# teensyLC-midi-IO_01.net
KiCad netlist of a schematic drawn in EAGLE
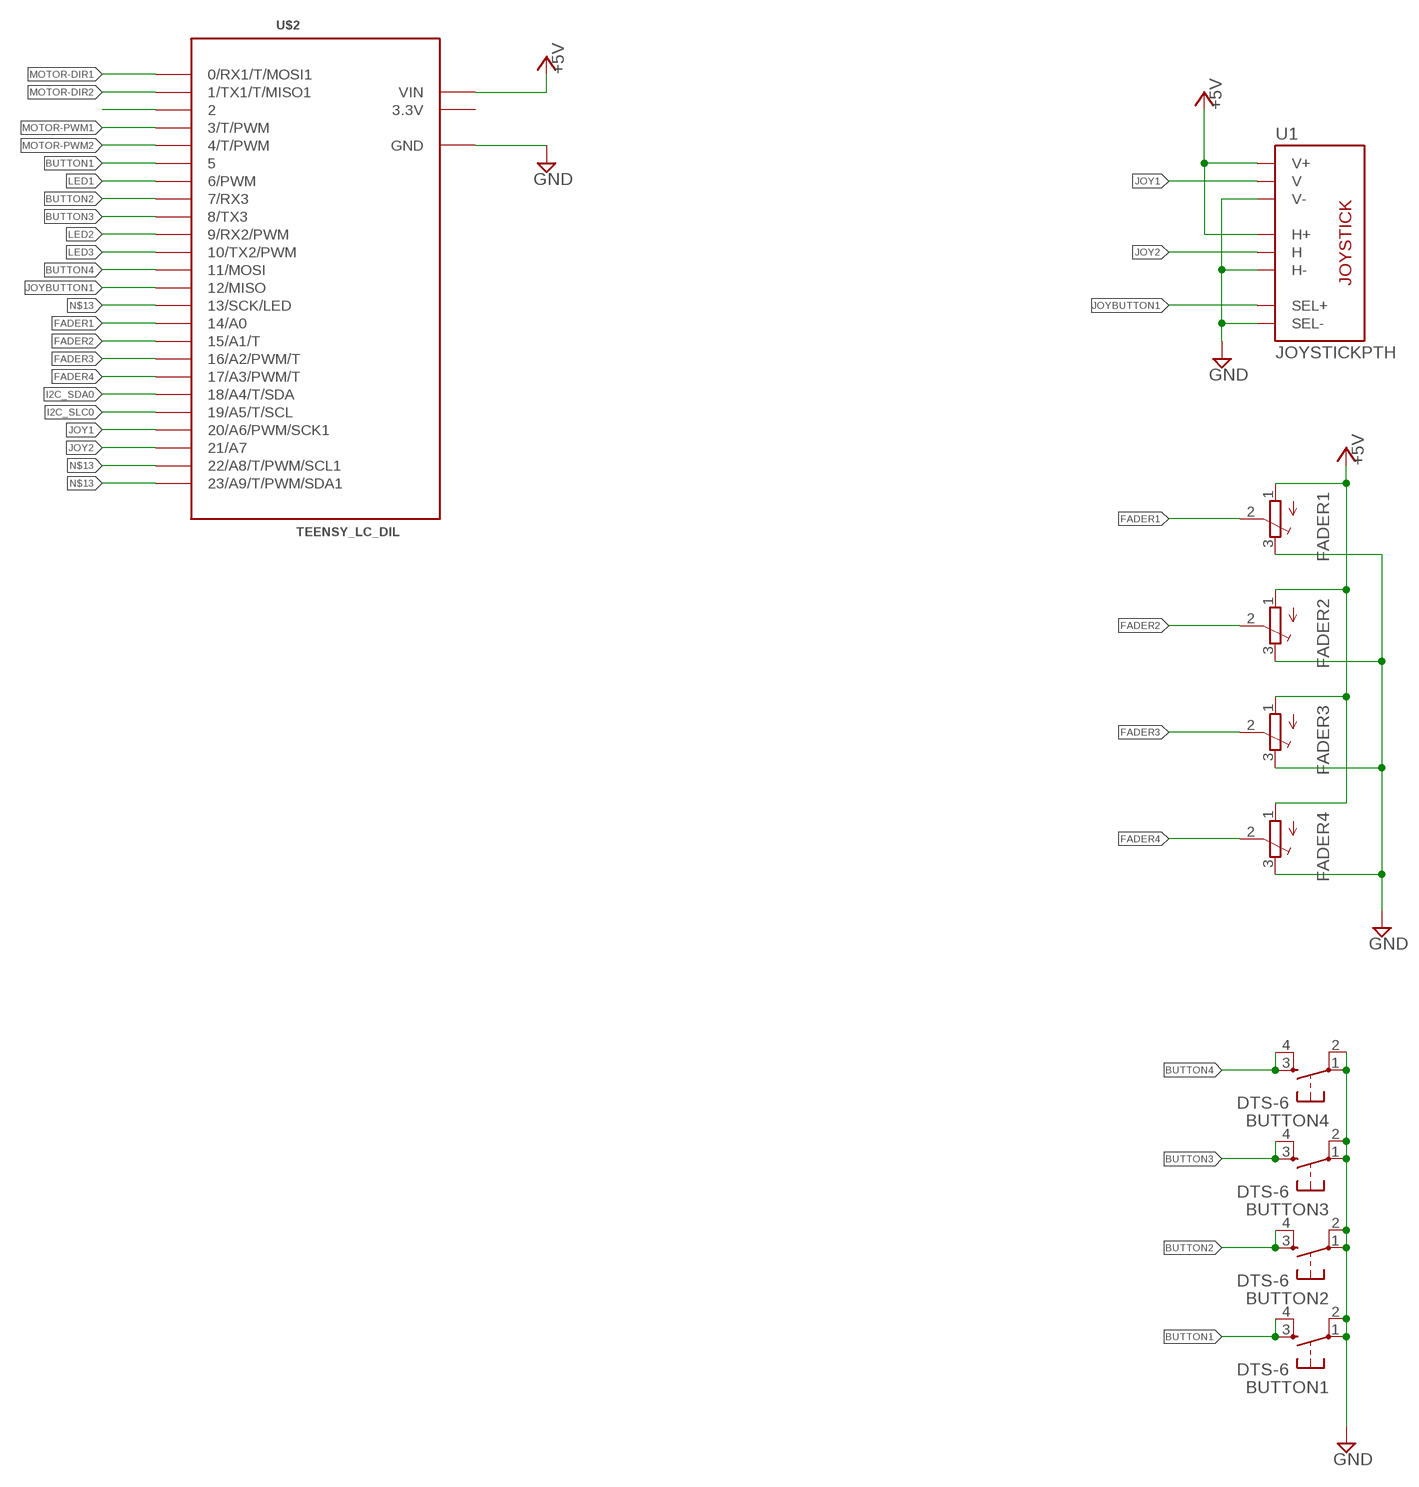
[diagram p0: schematic, sheet 1]

(export (version "E")
  (design (tool "Eeschema 10.0.6"))
  (components
    (comp (ref "BUTTON1")
      (value "DTS-6")
      (footprint "eagle-import:DTS-6")
      (libsource (lib "eagle-import") (part "DTS-6"))
    )
    (comp (ref "BUTTON2")
      (value "DTS-6")
      (footprint "eagle-import:DTS-6")
      (libsource (lib "eagle-import") (part "DTS-6"))
    )
    (comp (ref "BUTTON3")
      (value "DTS-6")
      (footprint "eagle-import:DTS-6")
      (libsource (lib "eagle-import") (part "DTS-6"))
    )
    (comp (ref "BUTTON4")
      (value "DTS-6")
      (footprint "eagle-import:DTS-6")
      (libsource (lib "eagle-import") (part "DTS-6"))
    )
    (comp (ref "FADER1")
      (value "TRIMPOT3386")
      (footprint "eagle-import:TRIM-3386")
      (libsource (lib "eagle-import") (part "TRIMPOT3386"))
    )
    (comp (ref "FADER2")
      (value "TRIMPOT3386")
      (footprint "eagle-import:TRIM-3386")
      (libsource (lib "eagle-import") (part "TRIMPOT3386"))
    )
    (comp (ref "FADER3")
      (value "TRIMPOT3386")
      (footprint "eagle-import:TRIM-3386")
      (libsource (lib "eagle-import") (part "TRIMPOT3386"))
    )
    (comp (ref "FADER4")
      (value "TRIMPOT3386")
      (footprint "eagle-import:TRIM-3386")
      (libsource (lib "eagle-import") (part "TRIMPOT3386"))
    )
    (comp (ref "U$2")
      (value "TEENSY_LC_DIL")
      (footprint "eagle-import:TEENSY_3.0-3.2&LC_DIL")
      (libsource (lib "eagle-import") (part "TEENSY_LC_DIL"))
    )
    (comp (ref "U1")
      (value "JOYSTICKPTH")
      (footprint "eagle-import:JOYSTICK")
      (libsource (lib "eagle-import") (part "JOYSTICKPTH"))
    )
  )
  (nets
    (net (code "1") (name "+5V") (class "Default")
      (node (ref "FADER1") (pin "1") (pinfunction "A_1") (pintype "passive"))
      (node (ref "FADER2") (pin "1") (pinfunction "A_1") (pintype "passive"))
      (node (ref "FADER3") (pin "1") (pinfunction "A_1") (pintype "passive"))
      (node (ref "FADER4") (pin "1") (pinfunction "A_1") (pintype "passive"))
      (node (ref "U$2") (pin "VIN") (pinfunction "VIN_VIN") (pintype "power_in"))
      (node (ref "U1") (pin "H1") (pinfunction "H+_H1") (pintype "bidirectional"))
      (node (ref "U1") (pin "V1") (pinfunction "V+_V1") (pintype "bidirectional"))
    )
    (net (code "2") (name "/3.3V") (class "Default")
      (node (ref "U$2") (pin "3.3V") (pinfunction "3.3V_3.3V") (pintype "power_in"))
    )
    (net (code "3") (name "BUTTON1") (class "Default")
      (node (ref "BUTTON1") (pin "3") (pinfunction "3_3") (pintype "passive"))
      (node (ref "BUTTON1") (pin "4") (pinfunction "4_4") (pintype "passive"))
      (node (ref "U$2") (pin "2") (pinfunction "2_2") (pintype "bidirectional"))
      (node (ref "U$2") (pin "5") (pinfunction "5_5") (pintype "bidirectional"))
    )
    (net (code "4") (name "BUTTON2") (class "Default")
      (node (ref "BUTTON2") (pin "3") (pinfunction "3_3") (pintype "passive"))
      (node (ref "BUTTON2") (pin "4") (pinfunction "4_4") (pintype "passive"))
      (node (ref "U$2") (pin "7") (pinfunction "7/RX3_7") (pintype "bidirectional"))
    )
    (net (code "5") (name "BUTTON3") (class "Default")
      (node (ref "BUTTON3") (pin "3") (pinfunction "3_3") (pintype "passive"))
      (node (ref "BUTTON3") (pin "4") (pinfunction "4_4") (pintype "passive"))
      (node (ref "U$2") (pin "8") (pinfunction "8/TX3_8") (pintype "bidirectional"))
    )
    (net (code "6") (name "BUTTON4") (class "Default")
      (node (ref "BUTTON4") (pin "3") (pinfunction "3_3") (pintype "passive"))
      (node (ref "BUTTON4") (pin "4") (pinfunction "4_4") (pintype "passive"))
      (node (ref "U$2") (pin "11") (pinfunction "11/MOSI_11") (pintype "bidirectional"))
    )
    (net (code "7") (name "FADER1") (class "Default")
      (node (ref "FADER1") (pin "2") (pinfunction "S_2") (pintype "passive"))
      (node (ref "U$2") (pin "14/A0") (pinfunction "14/A0_14/A0") (pintype "bidirectional"))
    )
    (net (code "8") (name "FADER2") (class "Default")
      (node (ref "FADER2") (pin "2") (pinfunction "S_2") (pintype "passive"))
      (node (ref "U$2") (pin "15/A1") (pinfunction "15/A1/T_15/A1") (pintype "bidirectional"))
    )
    (net (code "9") (name "FADER3") (class "Default")
      (node (ref "FADER3") (pin "2") (pinfunction "S_2") (pintype "passive"))
      (node (ref "U$2") (pin "16/A2") (pinfunction "16/A2/PWM/T_16/A2") (pintype "bidirectional"))
    )
    (net (code "10") (name "FADER4") (class "Default")
      (node (ref "FADER4") (pin "2") (pinfunction "S_2") (pintype "passive"))
      (node (ref "U$2") (pin "17/A3") (pinfunction "17/A3/PWM/T_17/A3") (pintype "bidirectional"))
    )
    (net (code "11") (name "GND") (class "Default")
      (node (ref "BUTTON1") (pin "1") (pinfunction "1_1") (pintype "passive"))
      (node (ref "BUTTON1") (pin "2") (pinfunction "2_2") (pintype "passive"))
      (node (ref "BUTTON2") (pin "1") (pinfunction "1_1") (pintype "passive"))
      (node (ref "BUTTON2") (pin "2") (pinfunction "2_2") (pintype "passive"))
      (node (ref "BUTTON3") (pin "1") (pinfunction "1_1") (pintype "passive"))
      (node (ref "BUTTON3") (pin "2") (pinfunction "2_2") (pintype "passive"))
      (node (ref "BUTTON4") (pin "1") (pinfunction "1_1") (pintype "passive"))
      (node (ref "BUTTON4") (pin "2") (pinfunction "2_2") (pintype "passive"))
      (node (ref "FADER1") (pin "3") (pinfunction "E_3") (pintype "passive"))
      (node (ref "FADER2") (pin "3") (pinfunction "E_3") (pintype "passive"))
      (node (ref "FADER3") (pin "3") (pinfunction "E_3") (pintype "passive"))
      (node (ref "FADER4") (pin "3") (pinfunction "E_3") (pintype "passive"))
      (node (ref "U$2") (pin "AGND") (pinfunction "GND_AGND") (pintype "power_in"))
      (node (ref "U$2") (pin "GND") (pinfunction "GND_GND") (pintype "power_in"))
      (node (ref "U1") (pin "B2A") (pinfunction "SEL-_B2A") (pintype "bidirectional"))
      (node (ref "U1") (pin "H3") (pinfunction "H-_H3") (pintype "bidirectional"))
      (node (ref "U1") (pin "V3") (pinfunction "V-_V3") (pintype "bidirectional"))
    )
    (net (code "12") (name "I2C_SDA0") (class "Default")
      (node (ref "U$2") (pin "18/A4") (pinfunction "18/A4/T/SDA_18/A4") (pintype "bidirectional"))
    )
    (net (code "13") (name "I2C_SLC0") (class "Default")
      (node (ref "U$2") (pin "19/A5") (pinfunction "19/A5/T/SCL_19/A5") (pintype "bidirectional"))
    )
    (net (code "14") (name "JOY1") (class "Default")
      (node (ref "U$2") (pin "20/A6") (pinfunction "20/A6/PWM/SCK1_20/A6") (pintype "bidirectional"))
      (node (ref "U1") (pin "V2") (pinfunction "V_V2") (pintype "bidirectional"))
    )
    (net (code "15") (name "JOY2") (class "Default")
      (node (ref "U$2") (pin "21/A7") (pinfunction "21/A7_21/A7") (pintype "bidirectional"))
      (node (ref "U1") (pin "H2") (pinfunction "H_H2") (pintype "bidirectional"))
    )
    (net (code "16") (name "JOYBUTTON1") (class "Default")
      (node (ref "U$2") (pin "12") (pinfunction "12/MISO_12") (pintype "bidirectional"))
      (node (ref "U1") (pin "B1A") (pinfunction "SEL+_B1A") (pintype "bidirectional"))
    )
    (net (code "17") (name "LED1") (class "Default")
      (node (ref "U$2") (pin "6") (pinfunction "6/PWM_6") (pintype "bidirectional"))
    )
    (net (code "18") (name "LED2") (class "Default")
      (node (ref "U$2") (pin "9") (pinfunction "9/RX2/PWM_9") (pintype "bidirectional"))
    )
    (net (code "19") (name "LED3") (class "Default")
      (node (ref "U$2") (pin "10") (pinfunction "10/TX2/PWM_10") (pintype "bidirectional"))
    )
    (net (code "20") (name "MOTOR-DIR1") (class "Default")
      (node (ref "U$2") (pin "0") (pinfunction "0/RX1/T/MOSI1_0") (pintype "bidirectional"))
    )
    (net (code "21") (name "MOTOR-DIR2") (class "Default")
      (node (ref "U$2") (pin "1") (pinfunction "1/TX1/T/MISO1_1") (pintype "bidirectional"))
    )
    (net (code "22") (name "MOTOR-PWM1") (class "Default")
      (node (ref "U$2") (pin "3") (pinfunction "3/T/PWM_3") (pintype "bidirectional"))
    )
    (net (code "23") (name "MOTOR-PWM2") (class "Default")
      (node (ref "U$2") (pin "4") (pinfunction "4/T/PWM_4") (pintype "bidirectional"))
    )
    (net (code "24") (name "N$13") (class "Default")
      (node (ref "U$2") (pin "13") (pinfunction "13/SCK/LED_13") (pintype "bidirectional"))
      (node (ref "U$2") (pin "22/A8") (pinfunction "22/A8/T/PWM/SCL1_22/A8") (pintype "bidirectional"))
      (node (ref "U$2") (pin "23/A9") (pinfunction "23/A9/T/PWM/SDA1_23/A9") (pintype "bidirectional"))
    )
  )
)
